# Test_MainboardESP8266.net
KiCad netlist of a schematic drawn in EAGLE
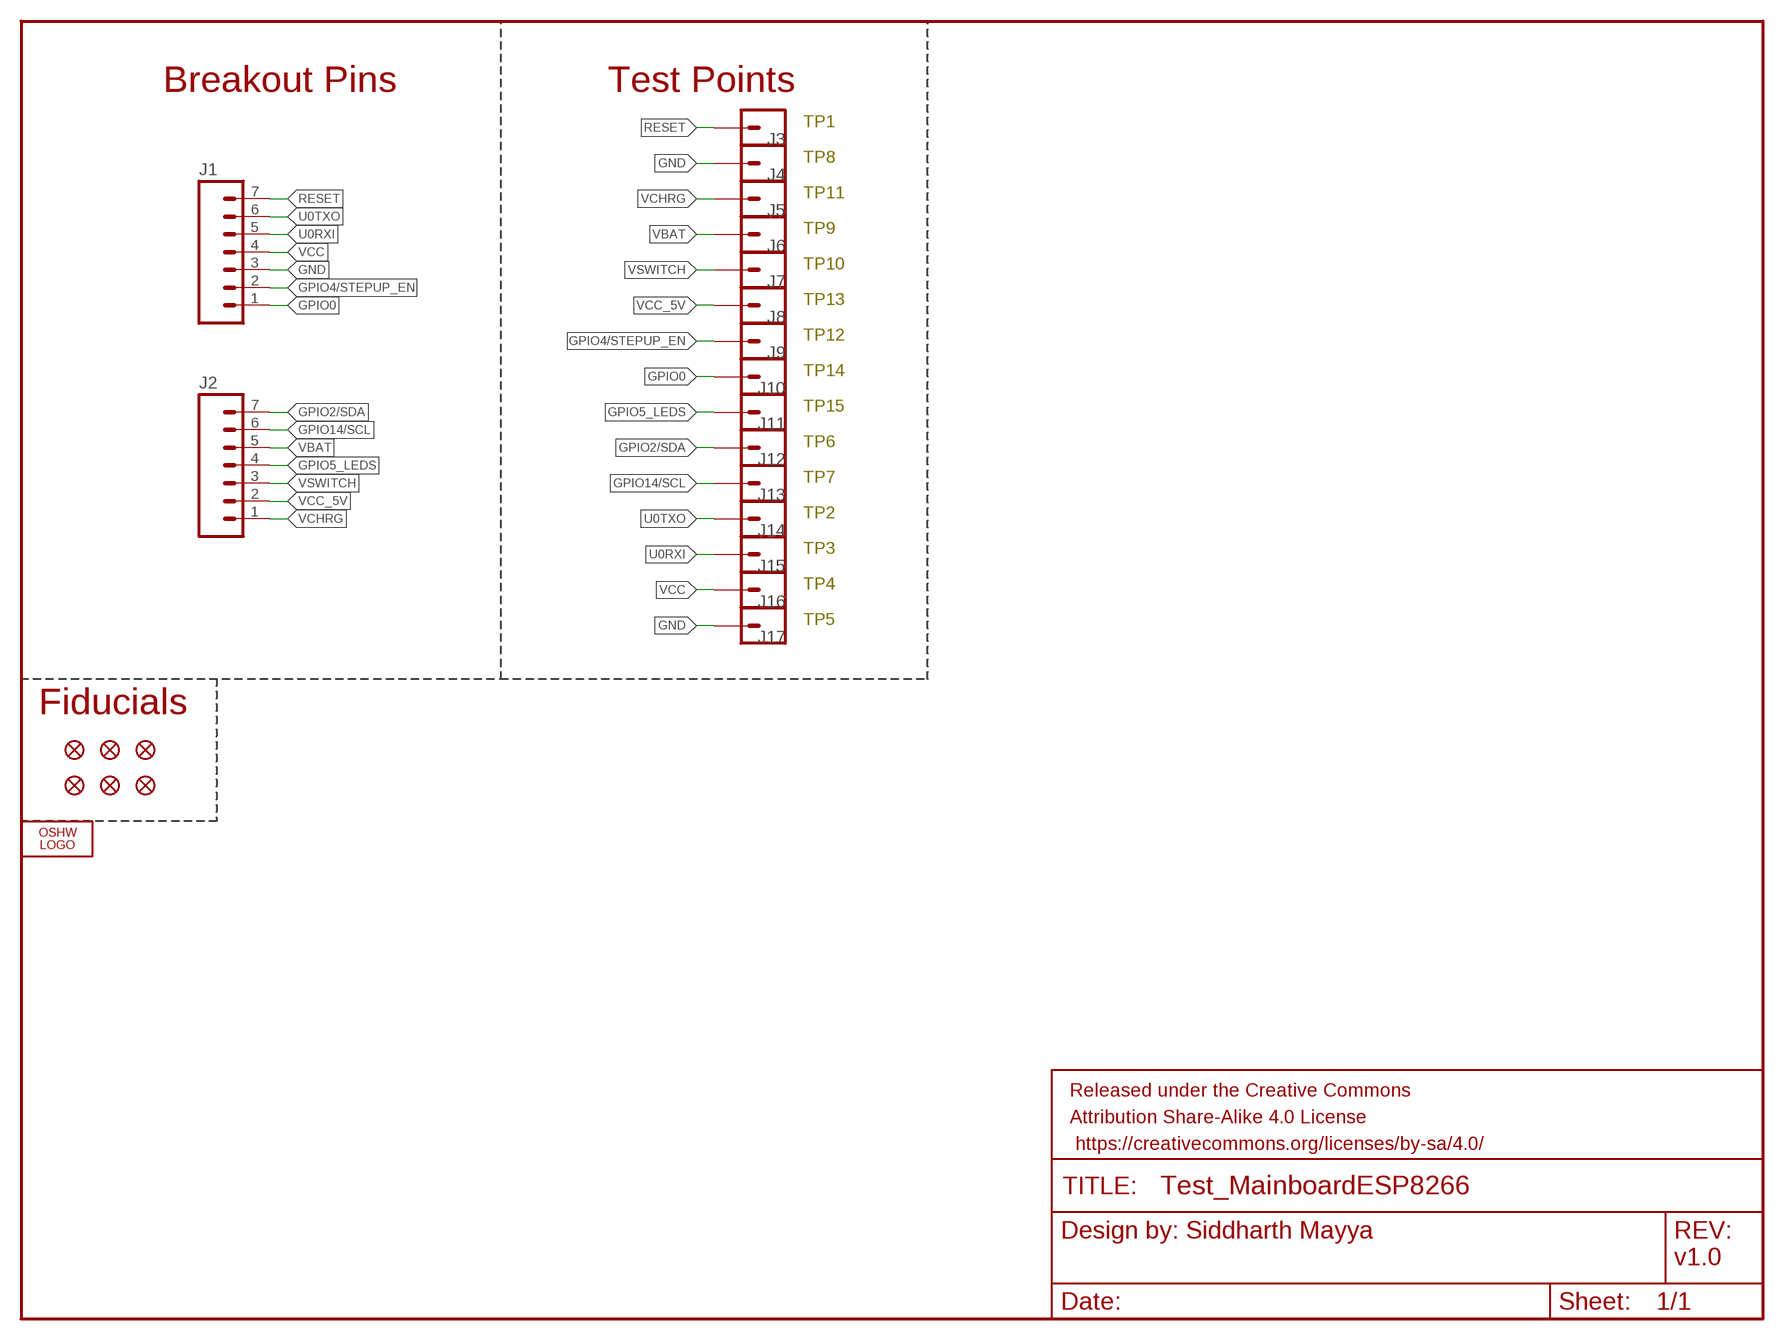
[diagram p0: schematic, sheet 1]

(export (version "E")
  (design (tool "Eeschema 10.0.6"))
  (components
    (comp (ref "FD1")
      (value "FIDUCIAL1X2")
      (footprint "eagle-import:FIDUCIAL-1X2")
      (libsource (lib "eagle-import") (part "FIDUCIAL1X2"))
    )
    (comp (ref "FD2")
      (value "FIDUCIAL1X2")
      (footprint "eagle-import:FIDUCIAL-1X2")
      (libsource (lib "eagle-import") (part "FIDUCIAL1X2"))
    )
    (comp (ref "FD3")
      (value "FIDUCIAL1X2")
      (footprint "eagle-import:FIDUCIAL-1X2")
      (libsource (lib "eagle-import") (part "FIDUCIAL1X2"))
    )
    (comp (ref "FD4")
      (value "FIDUCIAL1X2")
      (footprint "eagle-import:FIDUCIAL-1X2")
      (libsource (lib "eagle-import") (part "FIDUCIAL1X2"))
    )
    (comp (ref "FD5")
      (value "FIDUCIAL1X2")
      (footprint "eagle-import:FIDUCIAL-1X2")
      (libsource (lib "eagle-import") (part "FIDUCIAL1X2"))
    )
    (comp (ref "FD6")
      (value "FIDUCIAL1X2")
      (footprint "eagle-import:FIDUCIAL-1X2")
      (libsource (lib "eagle-import") (part "FIDUCIAL1X2"))
    )
    (comp (ref "FRAME1")
      (value "FRAME-LETTER")
      (footprint "eagle-import:CREATIVE_COMMONS")
      (libsource (lib "eagle-import") (part "FRAME-LETTER"))
    )
    (comp (ref "J1")
      (value "M07")
      (footprint "eagle-import:1X07")
      (libsource (lib "eagle-import") (part "M07"))
    )
    (comp (ref "J2")
      (value "M07")
      (footprint "eagle-import:1X07")
      (libsource (lib "eagle-import") (part "M07"))
    )
    (comp (ref "J3")
      (value "M01PTH")
      (footprint "eagle-import:1X01")
      (libsource (lib "eagle-import") (part "M01PTH"))
    )
    (comp (ref "J4")
      (value "M01PTH")
      (footprint "eagle-import:1X01")
      (libsource (lib "eagle-import") (part "M01PTH"))
    )
    (comp (ref "J5")
      (value "M01PTH")
      (footprint "eagle-import:1X01")
      (libsource (lib "eagle-import") (part "M01PTH"))
    )
    (comp (ref "J6")
      (value "M01PTH")
      (footprint "eagle-import:1X01")
      (libsource (lib "eagle-import") (part "M01PTH"))
    )
    (comp (ref "J7")
      (value "M01PTH")
      (footprint "eagle-import:1X01")
      (libsource (lib "eagle-import") (part "M01PTH"))
    )
    (comp (ref "J8")
      (value "M01PTH")
      (footprint "eagle-import:1X01")
      (libsource (lib "eagle-import") (part "M01PTH"))
    )
    (comp (ref "J9")
      (value "M01PTH")
      (footprint "eagle-import:1X01")
      (libsource (lib "eagle-import") (part "M01PTH"))
    )
    (comp (ref "J10")
      (value "M01PTH")
      (footprint "eagle-import:1X01")
      (libsource (lib "eagle-import") (part "M01PTH"))
    )
    (comp (ref "J11")
      (value "M01PTH")
      (footprint "eagle-import:1X01")
      (libsource (lib "eagle-import") (part "M01PTH"))
    )
    (comp (ref "J12")
      (value "M01PTH")
      (footprint "eagle-import:1X01")
      (libsource (lib "eagle-import") (part "M01PTH"))
    )
    (comp (ref "J13")
      (value "M01PTH")
      (footprint "eagle-import:1X01")
      (libsource (lib "eagle-import") (part "M01PTH"))
    )
    (comp (ref "J14")
      (value "M01PTH")
      (footprint "eagle-import:1X01")
      (libsource (lib "eagle-import") (part "M01PTH"))
    )
    (comp (ref "J15")
      (value "M01PTH")
      (footprint "eagle-import:1X01")
      (libsource (lib "eagle-import") (part "M01PTH"))
    )
    (comp (ref "J16")
      (value "M01PTH")
      (footprint "eagle-import:1X01")
      (libsource (lib "eagle-import") (part "M01PTH"))
    )
    (comp (ref "J17")
      (value "M01PTH")
      (footprint "eagle-import:1X01")
      (libsource (lib "eagle-import") (part "M01PTH"))
    )
    (comp (ref "LOGO1")
      (value "OSHW_LOGO_FILLX0100-NT")
      (footprint "eagle-import:OSHW_FILLX100_NOTEXT")
      (libsource (lib "eagle-import") (part "OSHW_LOGO_FILLX0100-NT"))
    )
  )
  (nets
    (net (code "1") (name "GND") (class "Default")
      (node (ref "J1") (pin "3") (pinfunction "3_3") (pintype "passive"))
      (node (ref "J17") (pin "1") (pinfunction "1_1") (pintype "passive"))
      (node (ref "J4") (pin "1") (pinfunction "1_1") (pintype "passive"))
    )
    (net (code "2") (name "GPIO0") (class "Default")
      (node (ref "J1") (pin "1") (pinfunction "1_1") (pintype "passive"))
      (node (ref "J10") (pin "1") (pinfunction "1_1") (pintype "passive"))
    )
    (net (code "3") (name "GPIO2{slash}SDA") (class "Default")
      (node (ref "J12") (pin "1") (pinfunction "1_1") (pintype "passive"))
      (node (ref "J2") (pin "7") (pinfunction "7_7") (pintype "passive"))
    )
    (net (code "4") (name "GPIO4{slash}STEPUP_EN") (class "Default")
      (node (ref "J1") (pin "2") (pinfunction "2_2") (pintype "passive"))
      (node (ref "J9") (pin "1") (pinfunction "1_1") (pintype "passive"))
    )
    (net (code "5") (name "GPIO5_LEDS") (class "Default")
      (node (ref "J11") (pin "1") (pinfunction "1_1") (pintype "passive"))
      (node (ref "J2") (pin "4") (pinfunction "4_4") (pintype "passive"))
    )
    (net (code "6") (name "GPIO14{slash}SCL") (class "Default")
      (node (ref "J13") (pin "1") (pinfunction "1_1") (pintype "passive"))
      (node (ref "J2") (pin "6") (pinfunction "6_6") (pintype "passive"))
    )
    (net (code "7") (name "RESET") (class "Default")
      (node (ref "J1") (pin "7") (pinfunction "7_7") (pintype "passive"))
      (node (ref "J3") (pin "1") (pinfunction "1_1") (pintype "passive"))
    )
    (net (code "8") (name "U0RXI") (class "Default")
      (node (ref "J1") (pin "5") (pinfunction "5_5") (pintype "passive"))
      (node (ref "J15") (pin "1") (pinfunction "1_1") (pintype "passive"))
    )
    (net (code "9") (name "U0TXO") (class "Default")
      (node (ref "J1") (pin "6") (pinfunction "6_6") (pintype "passive"))
      (node (ref "J14") (pin "1") (pinfunction "1_1") (pintype "passive"))
    )
    (net (code "10") (name "VBAT") (class "Default")
      (node (ref "J2") (pin "5") (pinfunction "5_5") (pintype "passive"))
      (node (ref "J6") (pin "1") (pinfunction "1_1") (pintype "passive"))
    )
    (net (code "11") (name "VCC") (class "Default")
      (node (ref "J1") (pin "4") (pinfunction "4_4") (pintype "passive"))
      (node (ref "J16") (pin "1") (pinfunction "1_1") (pintype "passive"))
    )
    (net (code "12") (name "VCC_5V") (class "Default")
      (node (ref "J2") (pin "2") (pinfunction "2_2") (pintype "passive"))
      (node (ref "J8") (pin "1") (pinfunction "1_1") (pintype "passive"))
    )
    (net (code "13") (name "VCHRG") (class "Default")
      (node (ref "J2") (pin "1") (pinfunction "1_1") (pintype "passive"))
      (node (ref "J5") (pin "1") (pinfunction "1_1") (pintype "passive"))
    )
    (net (code "14") (name "VSWITCH") (class "Default")
      (node (ref "J2") (pin "3") (pinfunction "3_3") (pintype "passive"))
      (node (ref "J7") (pin "1") (pinfunction "1_1") (pintype "passive"))
    )
  )
)
